# learning_zumo.net
KiCad netlist of a schematic drawn in EAGLE
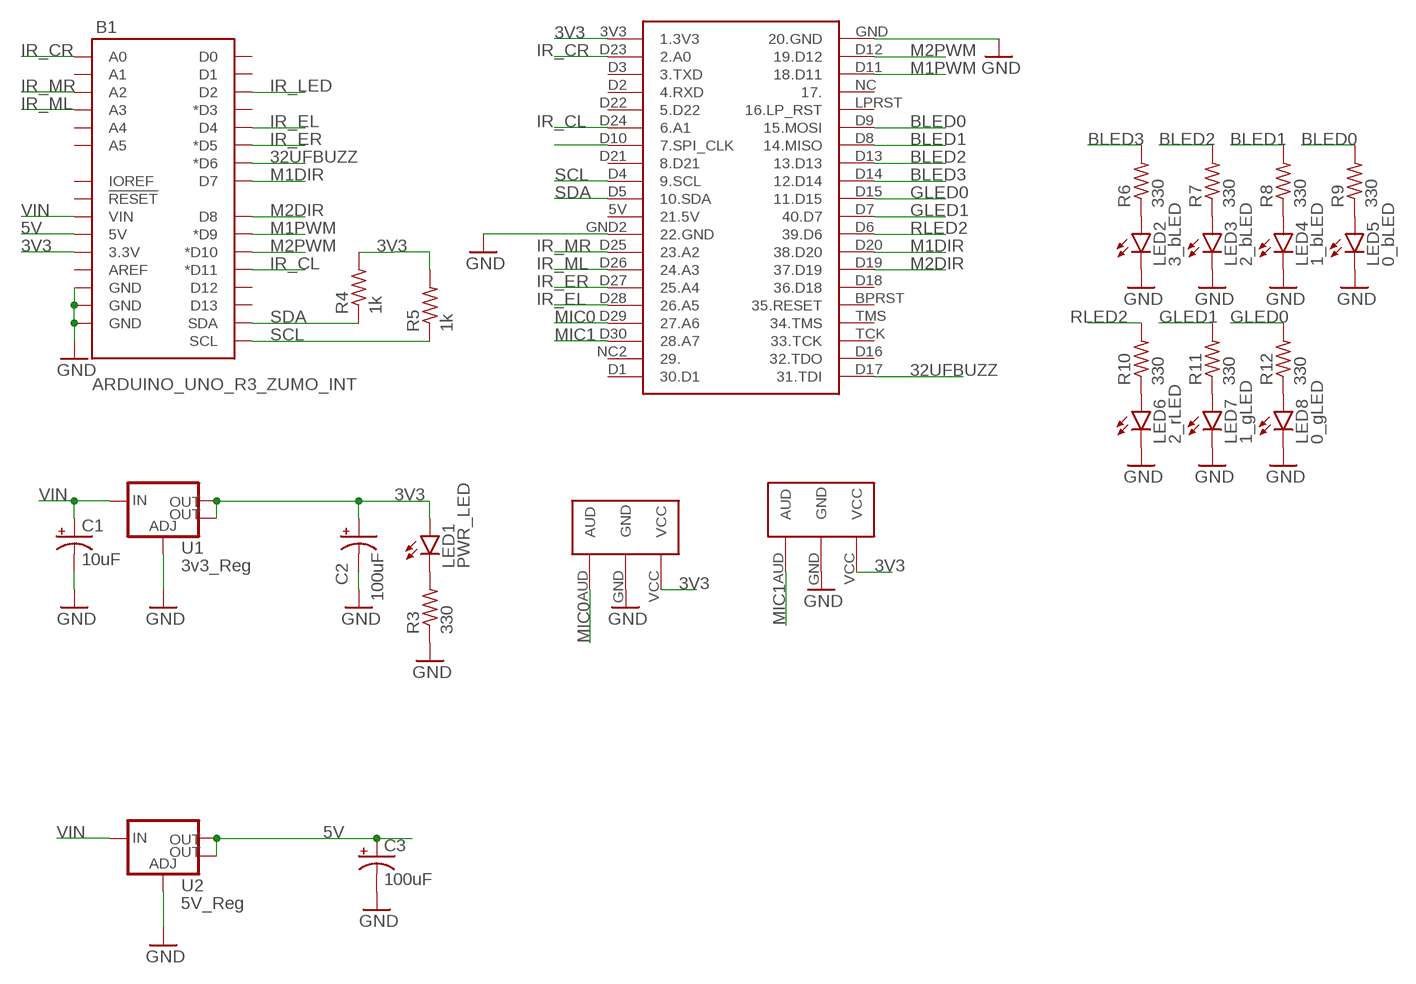
[diagram p0: schematic, sheet 1]

(export (version "E")
  (design (tool "Eeschema 10.0.6"))
  (components
    (comp (ref "B1")
      (value "ARDUINO_UNO_R3_ZUMO_INT")
      (footprint "eagle-import:UNO_R3_SHIELD_ICSP")
      (libsource (lib "eagle-import") (part "ARDUINO_UNO_R3_ZUMO_INT"))
    )
    (comp (ref "C1")
      (value "10uF")
      (footprint "eagle-import:E2,5-5")
      (libsource (lib "eagle-import") (part "CPOL-USE2.5-5"))
    )
    (comp (ref "C2")
      (value "100uF")
      (footprint "eagle-import:E2,5-5")
      (libsource (lib "eagle-import") (part "CPOL-USE2.5-5"))
    )
    (comp (ref "C3")
      (value "100uF")
      (footprint "eagle-import:E2,5-5")
      (libsource (lib "eagle-import") (part "CPOL-USE2.5-5"))
    )
    (comp (ref "LED1")
      (value "PWR_LED")
      (footprint "eagle-import:LED5MM")
      (libsource (lib "eagle-import") (part "LED5MM"))
    )
    (comp (ref "LED2")
      (value "3_bLED")
      (footprint "eagle-import:LED5MM")
      (libsource (lib "eagle-import") (part "LED5MM"))
    )
    (comp (ref "LED3")
      (value "2_bLED")
      (footprint "eagle-import:LED5MM")
      (libsource (lib "eagle-import") (part "LED5MM"))
    )
    (comp (ref "LED4")
      (value "1_bLED")
      (footprint "eagle-import:LED5MM")
      (libsource (lib "eagle-import") (part "LED5MM"))
    )
    (comp (ref "LED5")
      (value "0_bLED")
      (footprint "eagle-import:LED5MM")
      (libsource (lib "eagle-import") (part "LED5MM"))
    )
    (comp (ref "LED6")
      (value "2_rLED")
      (footprint "eagle-import:LED5MM")
      (libsource (lib "eagle-import") (part "LED5MM"))
    )
    (comp (ref "LED7")
      (value "1_gLED")
      (footprint "eagle-import:LED5MM")
      (libsource (lib "eagle-import") (part "LED5MM"))
    )
    (comp (ref "LED8")
      (value "0_gLED")
      (footprint "eagle-import:LED5MM")
      (libsource (lib "eagle-import") (part "LED5MM"))
    )
    (comp (ref "R3")
      (value "330")
      (footprint "eagle-import:0207_10")
      (libsource (lib "eagle-import") (part "R-US_0207/10"))
    )
    (comp (ref "R4")
      (value "1k")
      (footprint "eagle-import:0207_10")
      (libsource (lib "eagle-import") (part "R-US_0207/10"))
    )
    (comp (ref "R5")
      (value "1k")
      (footprint "eagle-import:0207_10")
      (libsource (lib "eagle-import") (part "R-US_0207/10"))
    )
    (comp (ref "R6")
      (value "330")
      (footprint "eagle-import:0207_10")
      (libsource (lib "eagle-import") (part "R-US_0207/10"))
    )
    (comp (ref "R7")
      (value "330")
      (footprint "eagle-import:0207_10")
      (libsource (lib "eagle-import") (part "R-US_0207/10"))
    )
    (comp (ref "R8")
      (value "330")
      (footprint "eagle-import:0207_10")
      (libsource (lib "eagle-import") (part "R-US_0207/10"))
    )
    (comp (ref "R9")
      (value "330")
      (footprint "eagle-import:0207_10")
      (libsource (lib "eagle-import") (part "R-US_0207/10"))
    )
    (comp (ref "R10")
      (value "330")
      (footprint "eagle-import:0207_10")
      (libsource (lib "eagle-import") (part "R-US_0207/10"))
    )
    (comp (ref "R11")
      (value "330")
      (footprint "eagle-import:0207_10")
      (libsource (lib "eagle-import") (part "R-US_0207/10"))
    )
    (comp (ref "R12")
      (value "330")
      (footprint "eagle-import:0207_10")
      (libsource (lib "eagle-import") (part "R-US_0207/10"))
    )
    (comp (ref "U$1")
      (value "CC1310_INT")
      (footprint "eagle-import:CC1310_INT")
      (libsource (lib "eagle-import") (part "CC1310_INT"))
    )
    (comp (ref "U$2")
      (value "ANALOG_MIC")
      (footprint "eagle-import:ANALOG_MIC")
      (libsource (lib "eagle-import") (part "ANALOG_MIC"))
    )
    (comp (ref "U$3")
      (value "ANALOG_MIC")
      (footprint "eagle-import:ANALOG_MIC")
      (libsource (lib "eagle-import") (part "ANALOG_MIC"))
    )
    (comp (ref "U1")
      (value "3v3_Reg")
      (footprint "eagle-import:NU32V7_SOT223")
      (libsource (lib "eagle-import") (part "NU32V7_V_REG_LM1117SOT223"))
    )
    (comp (ref "U2")
      (value "5V_Reg")
      (footprint "eagle-import:NU32V7_SOT223")
      (libsource (lib "eagle-import") (part "NU32V7_V_REG_LM1117SOT223"))
    )
  )
  (nets
    (net (code "1") (name "/3V3") (class "Default")
      (node (ref "B1") (pin "3.3V") (pinfunction "3.3V_3.3V") (pintype "bidirectional"))
      (node (ref "C2") (pin "+") (pinfunction "+_+") (pintype "passive"))
      (node (ref "LED1") (pin "A") (pinfunction "A_A") (pintype "passive"))
      (node (ref "R4") (pin "2") (pinfunction "2_2") (pintype "passive"))
      (node (ref "R5") (pin "2") (pinfunction "2_2") (pintype "passive"))
      (node (ref "U$1") (pin "3V3") (pinfunction "1.3V3_3V3") (pintype "bidirectional"))
      (node (ref "U$2") (pin "VCC") (pinfunction "VCC_VCC") (pintype "bidirectional"))
      (node (ref "U$3") (pin "VCC") (pinfunction "VCC_VCC") (pintype "bidirectional"))
      (node (ref "U1") (pin "OUTPUT") (pinfunction "OUT_OUTPUT") (pintype "output"))
      (node (ref "U1") (pin "VOUT") (pinfunction "OUT_VOUT") (pintype "output"))
    )
    (net (code "2") (name "/5V") (class "Default")
      (node (ref "B1") (pin "5V") (pinfunction "5V_5V") (pintype "bidirectional"))
      (node (ref "C3") (pin "+") (pinfunction "+_+") (pintype "passive"))
      (node (ref "U2") (pin "OUTPUT") (pinfunction "OUT_OUTPUT") (pintype "output"))
      (node (ref "U2") (pin "VOUT") (pinfunction "OUT_VOUT") (pintype "output"))
    )
    (net (code "3") (name "/32UFBUZZ") (class "Default")
      (node (ref "B1") (pin "D6") (pinfunction "*D6_D6") (pintype "bidirectional"))
      (node (ref "U$1") (pin "D17") (pinfunction "31.TDI_D17") (pintype "bidirectional"))
    )
    (net (code "4") (name "/BLED0") (class "Default")
      (node (ref "R9") (pin "2") (pinfunction "2_2") (pintype "passive"))
      (node (ref "U$1") (pin "D9") (pinfunction "15.MOSI_D9") (pintype "bidirectional"))
    )
    (net (code "5") (name "/BLED1") (class "Default")
      (node (ref "R8") (pin "2") (pinfunction "2_2") (pintype "passive"))
      (node (ref "U$1") (pin "D8") (pinfunction "14.MISO_D8") (pintype "bidirectional"))
    )
    (net (code "6") (name "/BLED2") (class "Default")
      (node (ref "R7") (pin "2") (pinfunction "2_2") (pintype "passive"))
      (node (ref "U$1") (pin "D13") (pinfunction "13.D13_D13") (pintype "bidirectional"))
    )
    (net (code "7") (name "/BLED3") (class "Default")
      (node (ref "R6") (pin "2") (pinfunction "2_2") (pintype "passive"))
      (node (ref "U$1") (pin "D14") (pinfunction "12.D14_D14") (pintype "bidirectional"))
    )
    (net (code "8") (name "/GLED0") (class "Default")
      (node (ref "R12") (pin "2") (pinfunction "2_2") (pintype "passive"))
      (node (ref "U$1") (pin "D15") (pinfunction "11.D15_D15") (pintype "bidirectional"))
    )
    (net (code "9") (name "/GLED1") (class "Default")
      (node (ref "R11") (pin "2") (pinfunction "2_2") (pintype "passive"))
      (node (ref "U$1") (pin "D7") (pinfunction "40.D7_D7") (pintype "bidirectional"))
    )
    (net (code "10") (name "/IR_CL") (class "Default")
      (node (ref "B1") (pin "D11") (pinfunction "*D11_D11") (pintype "bidirectional"))
      (node (ref "U$1") (pin "D24") (pinfunction "6.A1_D24") (pintype "bidirectional"))
    )
    (net (code "11") (name "/IR_CR") (class "Default")
      (node (ref "B1") (pin "A0") (pinfunction "A0_A0") (pintype "bidirectional"))
      (node (ref "U$1") (pin "D23") (pinfunction "2.A0_D23") (pintype "bidirectional"))
    )
    (net (code "12") (name "/IR_EL") (class "Default")
      (node (ref "B1") (pin "D4") (pinfunction "D4_D4") (pintype "bidirectional"))
      (node (ref "U$1") (pin "D28") (pinfunction "26.A5_D28") (pintype "bidirectional"))
    )
    (net (code "13") (name "/IR_ER") (class "Default")
      (node (ref "B1") (pin "D5") (pinfunction "*D5_D5") (pintype "bidirectional"))
      (node (ref "U$1") (pin "D27") (pinfunction "25.A4_D27") (pintype "bidirectional"))
    )
    (net (code "14") (name "/IR_LED") (class "Default")
      (node (ref "B1") (pin "D2") (pinfunction "D2_D2") (pintype "bidirectional"))
    )
    (net (code "15") (name "/IR_ML") (class "Default")
      (node (ref "B1") (pin "A3") (pinfunction "A3_A3") (pintype "bidirectional"))
      (node (ref "U$1") (pin "D26") (pinfunction "24.A3_D26") (pintype "bidirectional"))
    )
    (net (code "16") (name "/IR_MR") (class "Default")
      (node (ref "B1") (pin "A2") (pinfunction "A2_A2") (pintype "bidirectional"))
      (node (ref "U$1") (pin "D25") (pinfunction "23.A2_D25") (pintype "bidirectional"))
    )
    (net (code "17") (name "/M1DIR") (class "Default")
      (node (ref "B1") (pin "D7") (pinfunction "D7_D7") (pintype "bidirectional"))
      (node (ref "U$1") (pin "D20") (pinfunction "38.D20_D20") (pintype "bidirectional"))
    )
    (net (code "18") (name "/M1PWM") (class "Default")
      (node (ref "B1") (pin "D9") (pinfunction "*D9_D9") (pintype "bidirectional"))
      (node (ref "U$1") (pin "D11") (pinfunction "18.D11_D11") (pintype "bidirectional"))
    )
    (net (code "19") (name "/M2DIR") (class "Default")
      (node (ref "B1") (pin "D8") (pinfunction "D8_D8") (pintype "bidirectional"))
      (node (ref "U$1") (pin "D19") (pinfunction "37.D19_D19") (pintype "bidirectional"))
    )
    (net (code "20") (name "/M2PWM") (class "Default")
      (node (ref "B1") (pin "D10") (pinfunction "*D10_D10") (pintype "bidirectional"))
      (node (ref "U$1") (pin "D12") (pinfunction "19.D12_D12") (pintype "bidirectional"))
    )
    (net (code "21") (name "/MIC0") (class "Default")
      (node (ref "U$1") (pin "D29") (pinfunction "27.A6_D29") (pintype "bidirectional"))
      (node (ref "U$2") (pin "AUD") (pinfunction "AUD_AUD") (pintype "bidirectional"))
    )
    (net (code "22") (name "/MIC1") (class "Default")
      (node (ref "U$1") (pin "D30") (pinfunction "28.A7_D30") (pintype "bidirectional"))
      (node (ref "U$3") (pin "AUD") (pinfunction "AUD_AUD") (pintype "bidirectional"))
    )
    (net (code "23") (name "/RLED2") (class "Default")
      (node (ref "R10") (pin "2") (pinfunction "2_2") (pintype "passive"))
      (node (ref "U$1") (pin "D6") (pinfunction "39.D6_D6") (pintype "bidirectional"))
    )
    (net (code "24") (name "/SCL") (class "Default")
      (node (ref "B1") (pin "SCL") (pinfunction "SCL_SCL") (pintype "bidirectional"))
      (node (ref "R5") (pin "1") (pinfunction "1_1") (pintype "passive"))
      (node (ref "U$1") (pin "D4") (pinfunction "9.SCL_D4") (pintype "bidirectional"))
    )
    (net (code "25") (name "/SDA") (class "Default")
      (node (ref "B1") (pin "SDA") (pinfunction "SDA_SDA") (pintype "bidirectional"))
      (node (ref "R4") (pin "1") (pinfunction "1_1") (pintype "passive"))
      (node (ref "U$1") (pin "D5") (pinfunction "10.SDA_D5") (pintype "bidirectional"))
    )
    (net (code "26") (name "/VIN") (class "Default")
      (node (ref "B1") (pin "VIN") (pinfunction "VIN_VIN") (pintype "bidirectional"))
      (node (ref "C1") (pin "+") (pinfunction "+_+") (pintype "passive"))
      (node (ref "U1") (pin "INPUT") (pinfunction "IN_INPUT") (pintype "input"))
      (node (ref "U2") (pin "INPUT") (pinfunction "IN_INPUT") (pintype "input"))
    )
    (net (code "27") (name "GND") (class "Default")
      (node (ref "B1") (pin "GND@0") (pinfunction "GND_GND@0") (pintype "bidirectional"))
      (node (ref "B1") (pin "GND@1") (pinfunction "GND_GND@1") (pintype "bidirectional"))
      (node (ref "B1") (pin "GND@2") (pinfunction "GND_GND@2") (pintype "bidirectional"))
      (node (ref "C1") (pin "-") (pinfunction "-_-") (pintype "passive"))
      (node (ref "C2") (pin "-") (pinfunction "-_-") (pintype "passive"))
      (node (ref "C3") (pin "-") (pinfunction "-_-") (pintype "passive"))
      (node (ref "LED2") (pin "K") (pinfunction "C_K") (pintype "passive"))
      (node (ref "LED3") (pin "K") (pinfunction "C_K") (pintype "passive"))
      (node (ref "LED4") (pin "K") (pinfunction "C_K") (pintype "passive"))
      (node (ref "LED5") (pin "K") (pinfunction "C_K") (pintype "passive"))
      (node (ref "LED6") (pin "K") (pinfunction "C_K") (pintype "passive"))
      (node (ref "LED7") (pin "K") (pinfunction "C_K") (pintype "passive"))
      (node (ref "LED8") (pin "K") (pinfunction "C_K") (pintype "passive"))
      (node (ref "R3") (pin "1") (pinfunction "1_1") (pintype "passive"))
      (node (ref "U$1") (pin "GND") (pinfunction "20.GND_GND") (pintype "bidirectional"))
      (node (ref "U$1") (pin "GND2") (pinfunction "22.GND_GND2") (pintype "bidirectional"))
      (node (ref "U$2") (pin "GND") (pinfunction "GND_GND") (pintype "bidirectional"))
      (node (ref "U$3") (pin "GND") (pinfunction "GND_GND") (pintype "bidirectional"))
      (node (ref "U1") (pin "GND") (pinfunction "ADJ_GND") (pintype "input"))
      (node (ref "U2") (pin "GND") (pinfunction "ADJ_GND") (pintype "input"))
    )
    (net (code "28") (name "Net-(LED1-C)") (class "Default")
      (node (ref "LED1") (pin "K") (pinfunction "C_K") (pintype "passive"))
      (node (ref "R3") (pin "2") (pinfunction "2_2") (pintype "passive"))
    )
    (net (code "29") (name "Net-(LED2-PadA)") (class "Default")
      (node (ref "LED2") (pin "A") (pinfunction "A_A") (pintype "passive"))
      (node (ref "R6") (pin "1") (pinfunction "1_1") (pintype "passive"))
    )
    (net (code "30") (name "Net-(LED3-PadA)") (class "Default")
      (node (ref "LED3") (pin "A") (pinfunction "A_A") (pintype "passive"))
      (node (ref "R7") (pin "1") (pinfunction "1_1") (pintype "passive"))
    )
    (net (code "31") (name "Net-(LED4-PadA)") (class "Default")
      (node (ref "LED4") (pin "A") (pinfunction "A_A") (pintype "passive"))
      (node (ref "R8") (pin "1") (pinfunction "1_1") (pintype "passive"))
    )
    (net (code "32") (name "Net-(LED5-PadA)") (class "Default")
      (node (ref "LED5") (pin "A") (pinfunction "A_A") (pintype "passive"))
      (node (ref "R9") (pin "1") (pinfunction "1_1") (pintype "passive"))
    )
    (net (code "33") (name "Net-(LED6-PadA)") (class "Default")
      (node (ref "LED6") (pin "A") (pinfunction "A_A") (pintype "passive"))
      (node (ref "R10") (pin "1") (pinfunction "1_1") (pintype "passive"))
    )
    (net (code "34") (name "Net-(LED7-PadA)") (class "Default")
      (node (ref "LED7") (pin "A") (pinfunction "A_A") (pintype "passive"))
      (node (ref "R11") (pin "1") (pinfunction "1_1") (pintype "passive"))
    )
    (net (code "35") (name "Net-(LED8-PadA)") (class "Default")
      (node (ref "LED8") (pin "A") (pinfunction "A_A") (pintype "passive"))
      (node (ref "R12") (pin "1") (pinfunction "1_1") (pintype "passive"))
    )
    (net (code "36") (name "unconnected-(B1-*D3-PadD3)") (class "Default")
      (node (ref "B1") (pin "D3") (pinfunction "*D3_D3") (pintype "bidirectional"))
    )
    (net (code "37") (name "unconnected-(B1-D0-PadRX)") (class "Default")
      (node (ref "B1") (pin "RX") (pinfunction "D0_RX") (pintype "bidirectional"))
    )
    (net (code "38") (name "unconnected-(B1-D1-PadTX)") (class "Default")
      (node (ref "B1") (pin "TX") (pinfunction "D1_TX") (pintype "bidirectional"))
    )
    (net (code "39") (name "unconnected-(B1-PadA1)") (class "Default")
      (node (ref "B1") (pin "A1") (pinfunction "A1_A1") (pintype "bidirectional"))
    )
    (net (code "40") (name "unconnected-(B1-PadA4)") (class "Default")
      (node (ref "B1") (pin "A4") (pinfunction "A4_A4") (pintype "bidirectional"))
    )
    (net (code "41") (name "unconnected-(B1-PadA5)") (class "Default")
      (node (ref "B1") (pin "A5") (pinfunction "A5_A5") (pintype "bidirectional"))
    )
    (net (code "42") (name "unconnected-(B1-PadAREF)") (class "Default")
      (node (ref "B1") (pin "AREF") (pinfunction "AREF_AREF") (pintype "bidirectional"))
    )
    (net (code "43") (name "unconnected-(B1-PadD12)") (class "Default")
      (node (ref "B1") (pin "D12") (pinfunction "D12_D12") (pintype "bidirectional"))
    )
    (net (code "44") (name "unconnected-(B1-PadD13)") (class "Default")
      (node (ref "B1") (pin "D13") (pinfunction "D13_D13") (pintype "bidirectional"))
    )
    (net (code "45") (name "unconnected-(B1-PadIOREF)") (class "Default")
      (node (ref "B1") (pin "IOREF") (pinfunction "IOREF_IOREF") (pintype "bidirectional"))
    )
    (net (code "46") (name "unconnected-(B1-~{RESET}-PadRES)") (class "Default")
      (node (ref "B1") (pin "RES") (pinfunction "~{RESET}_RES") (pintype "bidirectional"))
    )
    (net (code "47") (name "unconnected-(U$1-3.TXD-PadD3)") (class "Default")
      (node (ref "U$1") (pin "D3") (pinfunction "3.TXD_D3") (pintype "bidirectional"))
    )
    (net (code "48") (name "unconnected-(U$1-4.RXD-PadD2)") (class "Default")
      (node (ref "U$1") (pin "D2") (pinfunction "4.RXD_D2") (pintype "bidirectional"))
    )
    (net (code "49") (name "unconnected-(U$1-5.D22-PadD22)") (class "Default")
      (node (ref "U$1") (pin "D22") (pinfunction "5.D22_D22") (pintype "bidirectional"))
    )
    (net (code "50") (name "unconnected-(U$1-7.SPI_CLK-PadD10)") (class "Default")
      (node (ref "U$1") (pin "D10") (pinfunction "7.SPI_CLK_D10") (pintype "bidirectional"))
    )
    (net (code "51") (name "unconnected-(U$1-8.D21-PadD21)") (class "Default")
      (node (ref "U$1") (pin "D21") (pinfunction "8.D21_D21") (pintype "bidirectional"))
    )
    (net (code "52") (name "unconnected-(U$1-16.LP_RST-PadLPRST)") (class "Default")
      (node (ref "U$1") (pin "LPRST") (pinfunction "16.LP_RST_LPRST") (pintype "bidirectional"))
    )
    (net (code "53") (name "unconnected-(U$1-17.-PadNC)") (class "Default")
      (node (ref "U$1") (pin "NC") (pinfunction "17._NC") (pintype "bidirectional"))
    )
    (net (code "54") (name "unconnected-(U$1-21.5V-Pad5V)") (class "Default")
      (node (ref "U$1") (pin "5V") (pinfunction "21.5V_5V") (pintype "bidirectional"))
    )
    (net (code "55") (name "unconnected-(U$1-29.-PadNC2)") (class "Default")
      (node (ref "U$1") (pin "NC2") (pinfunction "29._NC2") (pintype "bidirectional"))
    )
    (net (code "56") (name "unconnected-(U$1-30.D1-PadD1)") (class "Default")
      (node (ref "U$1") (pin "D1") (pinfunction "30.D1_D1") (pintype "bidirectional"))
    )
    (net (code "57") (name "unconnected-(U$1-32.TDO-PadD16)") (class "Default")
      (node (ref "U$1") (pin "D16") (pinfunction "32.TDO_D16") (pintype "bidirectional"))
    )
    (net (code "58") (name "unconnected-(U$1-33.TCK-PadTCK)") (class "Default")
      (node (ref "U$1") (pin "TCK") (pinfunction "33.TCK_TCK") (pintype "bidirectional"))
    )
    (net (code "59") (name "unconnected-(U$1-34.TMS-PadTMS)") (class "Default")
      (node (ref "U$1") (pin "TMS") (pinfunction "34.TMS_TMS") (pintype "bidirectional"))
    )
    (net (code "60") (name "unconnected-(U$1-35.RESET-PadBPRST)") (class "Default")
      (node (ref "U$1") (pin "BPRST") (pinfunction "35.RESET_BPRST") (pintype "bidirectional"))
    )
    (net (code "61") (name "unconnected-(U$1-36.D18-PadD18)") (class "Default")
      (node (ref "U$1") (pin "D18") (pinfunction "36.D18_D18") (pintype "bidirectional"))
    )
  )
)
